# top.net
KiCad netlist of a schematic drawn in Altium Designer
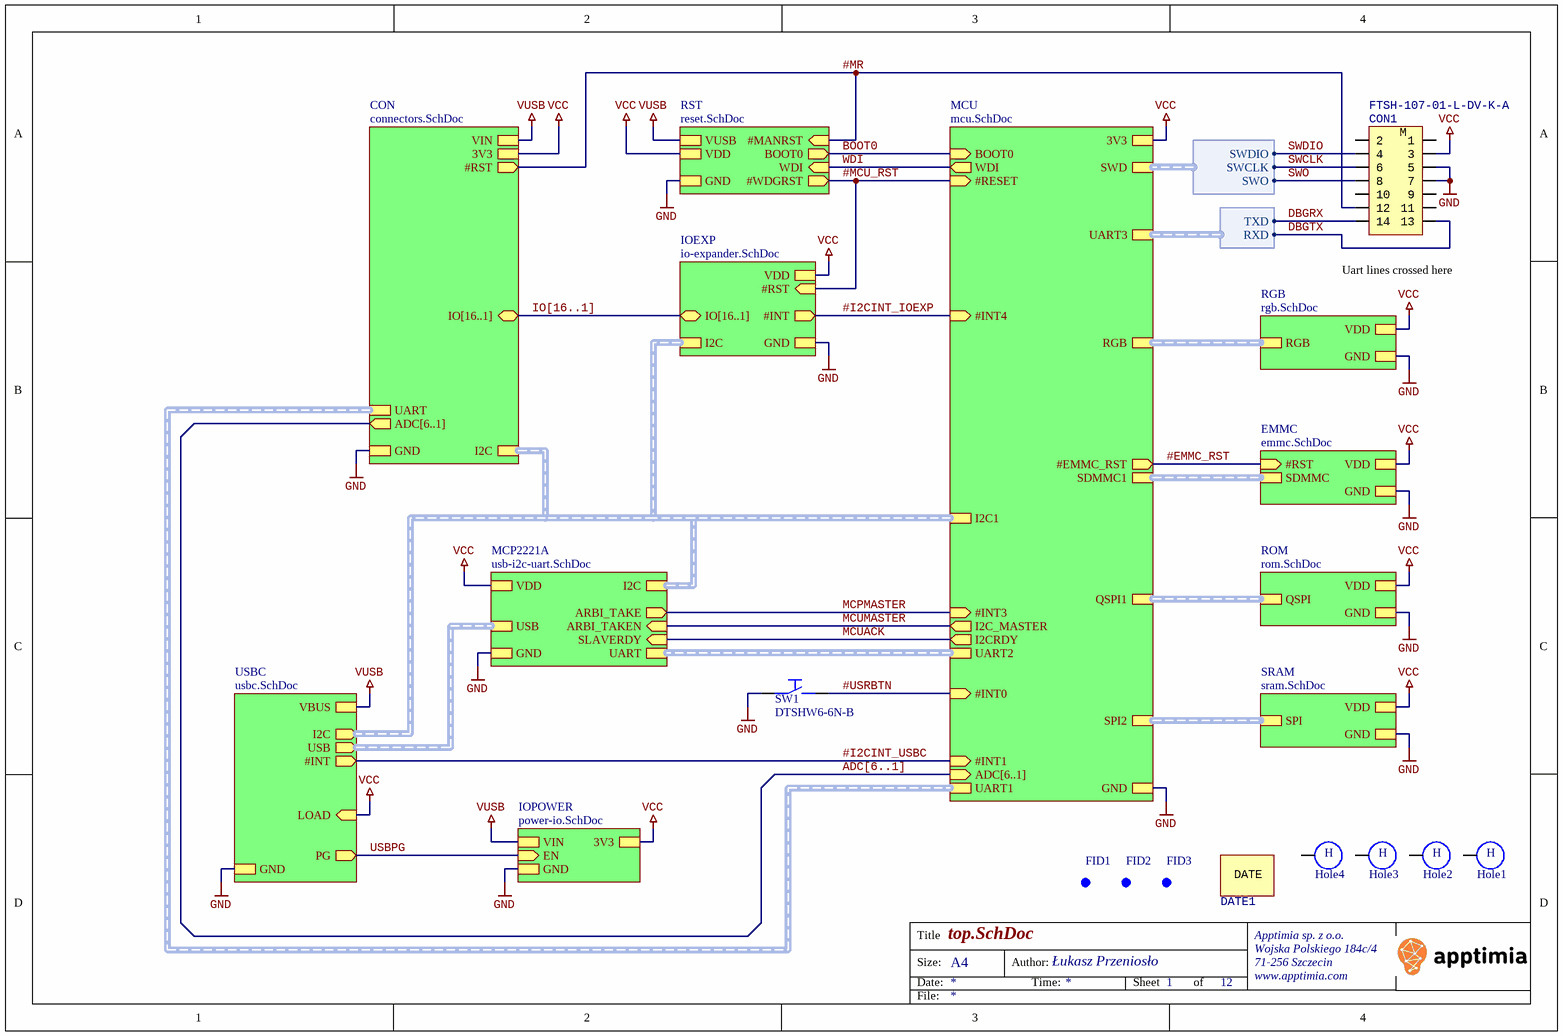
[diagram p0: top.SchDoc]

(export (version "E")
  (design (tool "Eeschema 10.0.6"))
  (components
    (comp (ref "CON1")
      (value "FTSH-107-01-L-DV-K-A")
      (footprint "CON_SAMTEC_FTSH-107-01-L-DV-K-A")
      (libsource (lib "connectors") (part "FTSH-107-01-L-DV-K-A"))
    )
    (comp (ref "DATE1") (value "DATE") (footprint "DATE") (libsource (lib "misc") (part "DATE")))
    (comp (ref "FID1") (value "Fiducial") (footprint "Fid Round") (libsource (lib "misc") (part "FID")))
    (comp (ref "FID2") (value "Fiducial") (footprint "Fid Round") (libsource (lib "misc") (part "FID")))
    (comp (ref "FID3") (value "Fiducial") (footprint "Fid Round") (libsource (lib "misc") (part "FID")))
    (comp (ref "Hole1") (value "Hole") (footprint "Hole-4/3.2") (libsource (lib "misc") (part "HOLE_")))
    (comp (ref "Hole2") (value "Hole") (footprint "Hole-4/3.2") (libsource (lib "misc") (part "HOLE_")))
    (comp (ref "Hole3") (value "Hole") (footprint "Hole-4/3.2") (libsource (lib "misc") (part "HOLE_")))
    (comp (ref "Hole4") (value "Hole") (footprint "Hole-4/3.2") (libsource (lib "misc") (part "HOLE_")))
    (comp (ref "SW1")
      (value "DTSHW6-6N-B")
      (footprint "FSM2J")
      (description "SWITCH, SPNO TACT")
      (fields (field (name "PUBLISHER") "Altium Limited"))
      (libsource (lib "btnsw") (part "DTSHW66NB"))
    )
  )
  (nets
    (net (code "29") (name "/#MR") (class "Default")
      (node (ref "CON1") (pin "12") (pinfunction "12_12") (pintype "passive"))
    )
    (net (code "30") (name "/#USRBTN") (class "Default")
      (node (ref "SW1") (pin "2") (pinfunction "2_2") (pintype "passive"))
    )
    (net (code "33") (name "/DBGRX") (class "Default")
      (node (ref "CON1") (pin "14") (pinfunction "14_14") (pintype "passive"))
    )
    (net (code "34") (name "/DBGTX") (class "Default")
      (node (ref "CON1") (pin "13") (pinfunction "13_13") (pintype "passive"))
    )
    (net (code "44") (name "/SWCLK") (class "Default")
      (node (ref "CON1") (pin "6") (pinfunction "6_6") (pintype "passive"))
    )
    (net (code "45") (name "/SWDIO") (class "Default")
      (node (ref "CON1") (pin "4") (pinfunction "4_4") (pintype "passive"))
    )
    (net (code "46") (name "/SWO") (class "Default")
      (node (ref "CON1") (pin "8") (pinfunction "8_8") (pintype "passive"))
    )
    (net (code "54") (name "GND") (class "Default")
      (node (ref "CON1") (pin "5") (pinfunction "5_5") (pintype "passive"))
      (node (ref "CON1") (pin "7") (pinfunction "7_7") (pintype "passive"))
      (node (ref "SW1") (pin "1") (pinfunction "1_1") (pintype "passive"))
    )
    (net (code "55") (name "VCC") (class "Default")
      (node (ref "CON1") (pin "3") (pinfunction "3_3") (pintype "passive"))
    )
    (net (code "57") (name "unconnected-(CON1-Pad1)") (class "Default")
      (node (ref "CON1") (pin "1") (pinfunction "1_1") (pintype "passive"))
    )
    (net (code "58") (name "unconnected-(CON1-Pad2)") (class "Default")
      (node (ref "CON1") (pin "2") (pinfunction "2_2") (pintype "passive"))
    )
    (net (code "59") (name "unconnected-(CON1-Pad9)") (class "Default")
      (node (ref "CON1") (pin "9") (pinfunction "9_9") (pintype "passive"))
    )
    (net (code "60") (name "unconnected-(CON1-Pad10)") (class "Default")
      (node (ref "CON1") (pin "10") (pinfunction "10_10") (pintype "passive"))
    )
    (net (code "61") (name "unconnected-(CON1-Pad11)") (class "Default")
      (node (ref "CON1") (pin "11") (pinfunction "11_11") (pintype "passive"))
    )
    (net (code "62") (name "unconnected-(Hole1-Pad1)") (class "Default")
      (node (ref "Hole1") (pin "1") (pinfunction "1_1") (pintype "passive"))
    )
    (net (code "63") (name "unconnected-(Hole2-Pad1)") (class "Default")
      (node (ref "Hole2") (pin "1") (pinfunction "1_1") (pintype "passive"))
    )
    (net (code "64") (name "unconnected-(Hole3-Pad1)") (class "Default")
      (node (ref "Hole3") (pin "1") (pinfunction "1_1") (pintype "passive"))
    )
    (net (code "65") (name "unconnected-(Hole4-Pad1)") (class "Default")
      (node (ref "Hole4") (pin "1") (pinfunction "1_1") (pintype "passive"))
    )
  )
)
